# QFN20.net
KiCad netlist of a schematic drawn in EAGLE
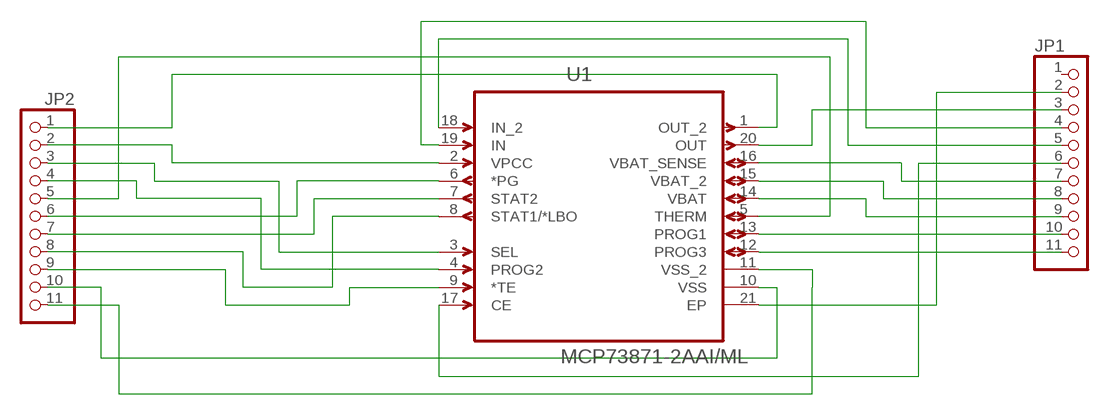
[diagram p0: schematic, sheet 1]

(export (version "E")
  (design (tool "Eeschema 10.0.6"))
  (components
    (comp (ref "JP1")
      (value "PINHD-1X11")
      (footprint "eagle-import:1X11")
      (libsource (lib "eagle-import") (part "PINHD-1X11"))
    )
    (comp (ref "JP2")
      (value "PINHD-1X11")
      (footprint "eagle-import:1X11")
      (libsource (lib "eagle-import") (part "PINHD-1X11"))
    )
    (comp (ref "U1")
      (value "MCP73871-2AAI/ML")
      (footprint "eagle-import:QFN50P400X400X100-21N")
      (libsource (lib "eagle-import") (part "MCP73871-2AAI/ML"))
    )
  )
  (nets
    (net (code "1") (name "Net-(U1-*PG)") (class "Default")
      (node (ref "JP2") (pin "6") (pinfunction "6_6") (pintype "passive"))
      (node (ref "U1") (pin "6") (pinfunction "*PG_6") (pintype "output"))
    )
    (net (code "2") (name "Net-(U1-*TE)") (class "Default")
      (node (ref "JP2") (pin "9") (pinfunction "9_9") (pintype "passive"))
      (node (ref "U1") (pin "9") (pinfunction "*TE_9") (pintype "input"))
    )
    (net (code "3") (name "Net-(U1-CE)") (class "Default")
      (node (ref "JP1") (pin "6") (pinfunction "6_6") (pintype "passive"))
      (node (ref "U1") (pin "17") (pinfunction "CE_17") (pintype "input"))
    )
    (net (code "4") (name "Net-(U1-EP)") (class "Default")
      (node (ref "JP1") (pin "2") (pinfunction "2_2") (pintype "passive"))
      (node (ref "U1") (pin "21") (pinfunction "EP_21") (pintype "passive"))
    )
    (net (code "5") (name "Net-(U1-IN)") (class "Default")
      (node (ref "JP1") (pin "4") (pinfunction "4_4") (pintype "passive"))
      (node (ref "U1") (pin "19") (pinfunction "IN_19") (pintype "input"))
    )
    (net (code "6") (name "Net-(U1-IN_2)") (class "Default")
      (node (ref "JP1") (pin "5") (pinfunction "5_5") (pintype "passive"))
      (node (ref "U1") (pin "18") (pinfunction "IN_2_18") (pintype "input"))
    )
    (net (code "7") (name "Net-(U1-OUT)") (class "Default")
      (node (ref "JP1") (pin "3") (pinfunction "3_3") (pintype "passive"))
      (node (ref "U1") (pin "20") (pinfunction "OUT_20") (pintype "output"))
    )
    (net (code "8") (name "Net-(U1-OUT_2)") (class "Default")
      (node (ref "JP2") (pin "1") (pinfunction "1_1") (pintype "passive"))
      (node (ref "U1") (pin "1") (pinfunction "OUT_2_1") (pintype "output"))
    )
    (net (code "9") (name "Net-(U1-PROG1)") (class "Default")
      (node (ref "JP1") (pin "10") (pinfunction "10_10") (pintype "passive"))
      (node (ref "U1") (pin "13") (pinfunction "PROG1_13") (pintype "bidirectional"))
    )
    (net (code "10") (name "Net-(U1-PROG2)") (class "Default")
      (node (ref "JP2") (pin "4") (pinfunction "4_4") (pintype "passive"))
      (node (ref "U1") (pin "4") (pinfunction "PROG2_4") (pintype "input"))
    )
    (net (code "11") (name "Net-(U1-PROG3)") (class "Default")
      (node (ref "JP1") (pin "11") (pinfunction "11_11") (pintype "passive"))
      (node (ref "U1") (pin "12") (pinfunction "PROG3_12") (pintype "bidirectional"))
    )
    (net (code "12") (name "Net-(U1-SEL)") (class "Default")
      (node (ref "JP2") (pin "3") (pinfunction "3_3") (pintype "passive"))
      (node (ref "U1") (pin "3") (pinfunction "SEL_3") (pintype "input"))
    )
    (net (code "13") (name "Net-(U1-STAT1{slash}*LBO)") (class "Default")
      (node (ref "JP2") (pin "8") (pinfunction "8_8") (pintype "passive"))
      (node (ref "U1") (pin "8") (pinfunction "STAT1/*LBO_8") (pintype "output"))
    )
    (net (code "14") (name "Net-(U1-STAT2)") (class "Default")
      (node (ref "JP2") (pin "7") (pinfunction "7_7") (pintype "passive"))
      (node (ref "U1") (pin "7") (pinfunction "STAT2_7") (pintype "output"))
    )
    (net (code "15") (name "Net-(U1-THERM)") (class "Default")
      (node (ref "JP2") (pin "5") (pinfunction "5_5") (pintype "passive"))
      (node (ref "U1") (pin "5") (pinfunction "THERM_5") (pintype "bidirectional"))
    )
    (net (code "16") (name "Net-(U1-VBAT)") (class "Default")
      (node (ref "JP1") (pin "9") (pinfunction "9_9") (pintype "passive"))
      (node (ref "U1") (pin "14") (pinfunction "VBAT_14") (pintype "bidirectional"))
    )
    (net (code "17") (name "Net-(U1-VBAT_2)") (class "Default")
      (node (ref "JP1") (pin "8") (pinfunction "8_8") (pintype "passive"))
      (node (ref "U1") (pin "15") (pinfunction "VBAT_2_15") (pintype "bidirectional"))
    )
    (net (code "18") (name "Net-(U1-VBAT_SENSE)") (class "Default")
      (node (ref "JP1") (pin "7") (pinfunction "7_7") (pintype "passive"))
      (node (ref "U1") (pin "16") (pinfunction "VBAT_SENSE_16") (pintype "bidirectional"))
    )
    (net (code "19") (name "Net-(U1-VPCC)") (class "Default")
      (node (ref "JP2") (pin "2") (pinfunction "2_2") (pintype "passive"))
      (node (ref "U1") (pin "2") (pinfunction "VPCC_2") (pintype "input"))
    )
    (net (code "20") (name "Net-(U1-VSS)") (class "Default")
      (node (ref "JP2") (pin "10") (pinfunction "10_10") (pintype "passive"))
      (node (ref "U1") (pin "10") (pinfunction "VSS_10") (pintype "power_in"))
    )
    (net (code "21") (name "Net-(U1-VSS_2)") (class "Default")
      (node (ref "JP2") (pin "11") (pinfunction "11_11") (pintype "passive"))
      (node (ref "U1") (pin "11") (pinfunction "VSS_2_11") (pintype "power_in"))
    )
    (net (code "22") (name "unconnected-(JP1-Pad1)") (class "Default")
      (node (ref "JP1") (pin "1") (pinfunction "1_1") (pintype "passive"))
    )
  )
)
